# SENSORES.net
KiCad netlist of a schematic drawn in EAGLE
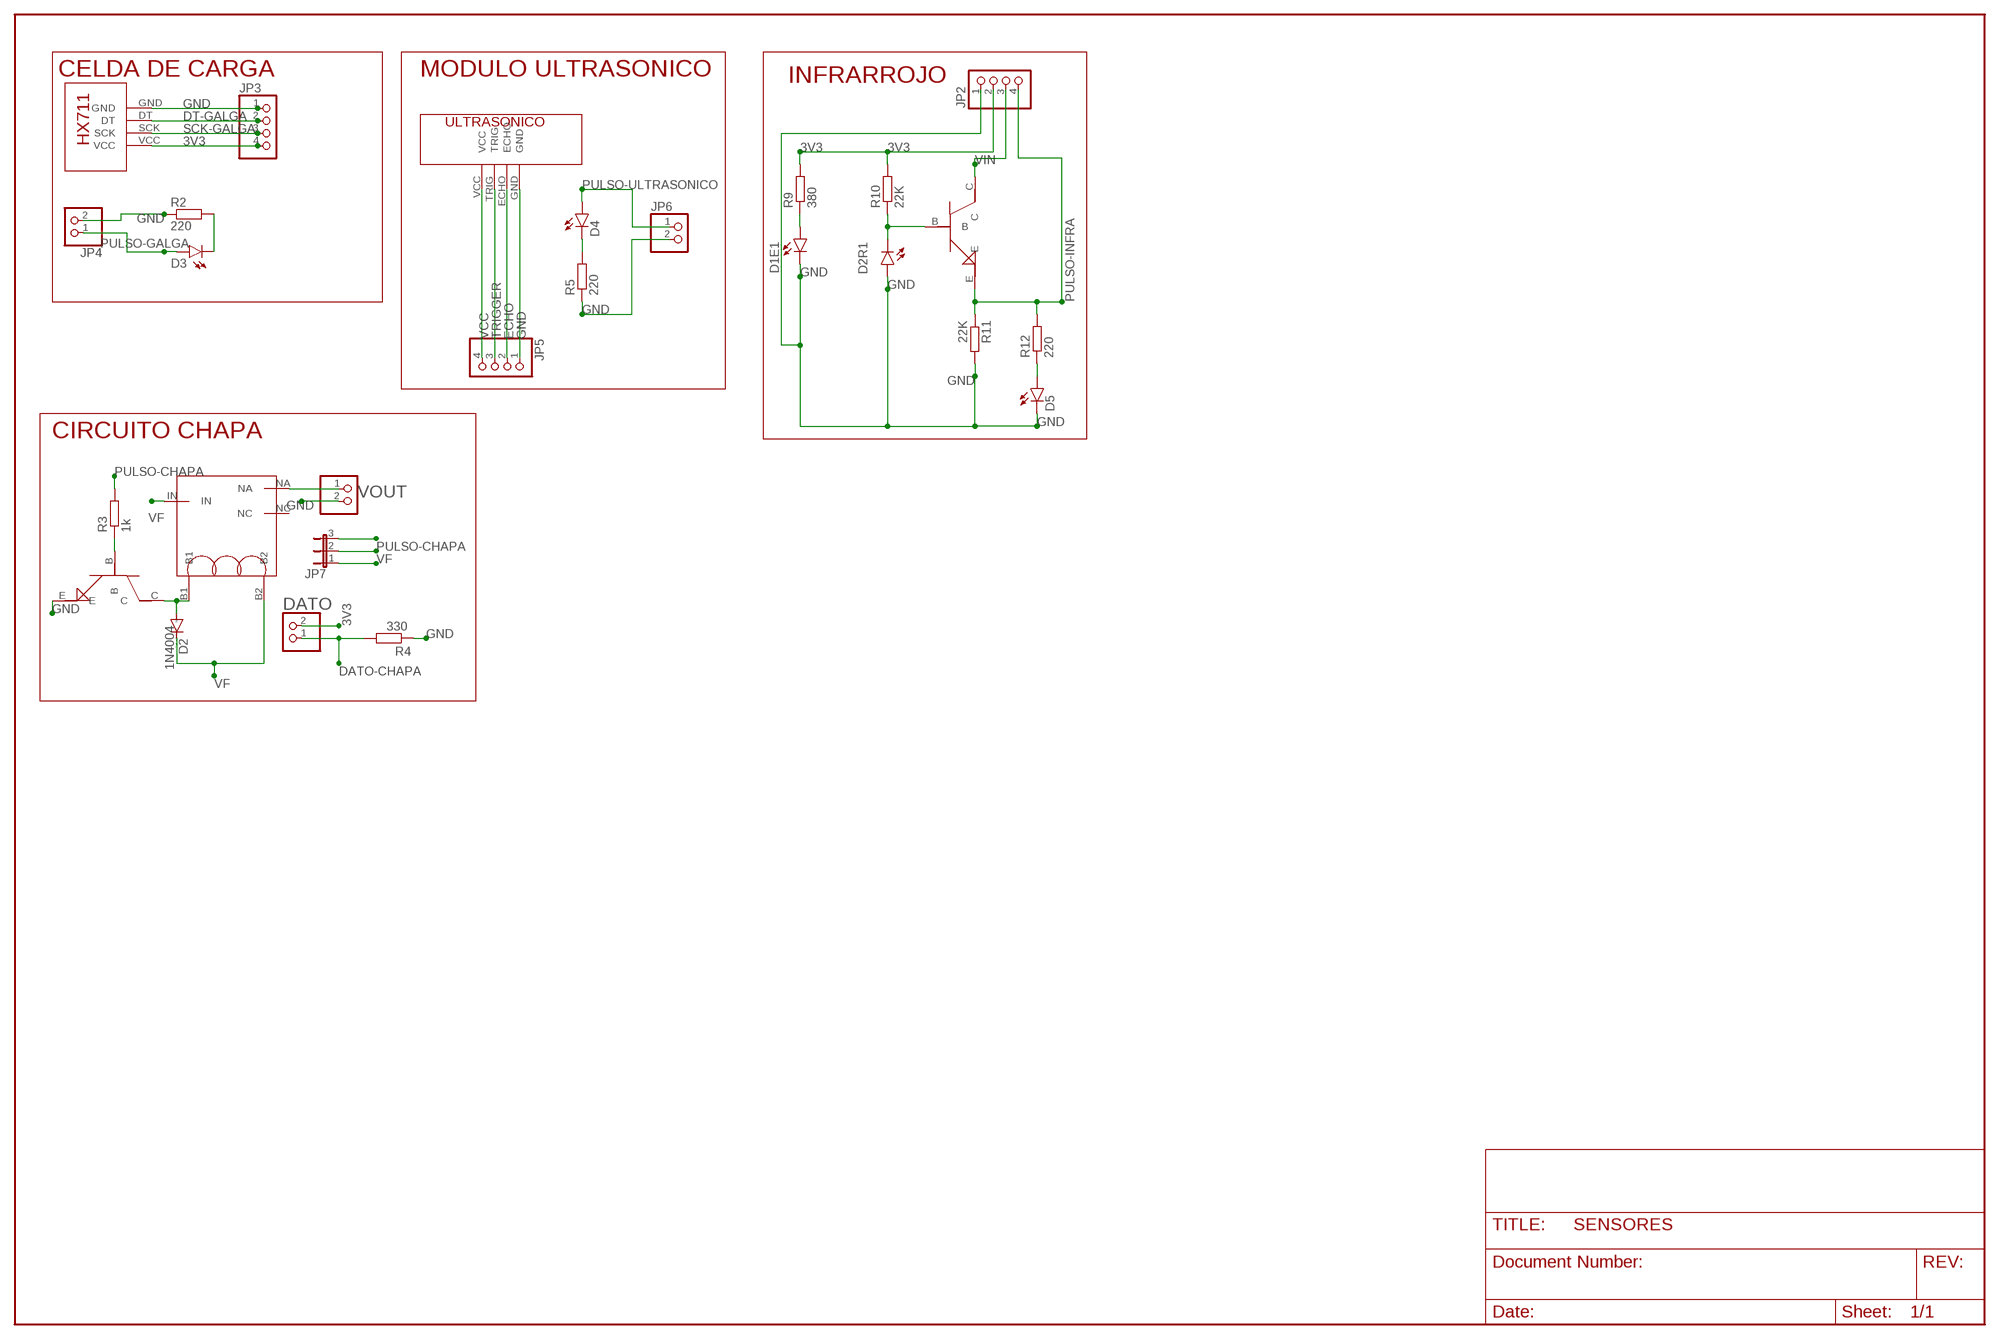
[diagram p0: schematic, sheet 1]

(export (version "E")
  (design (tool "Eeschema 10.0.6"))
  (components
    (comp (ref "D1E1")
      (value "LED3MM")
      (footprint "eagle-import:LED3MM")
      (libsource (lib "eagle-import") (part "LED3MM"))
    )
    (comp (ref "D2")
      (value "1N4004")
      (footprint "eagle-import:DO41-10")
      (libsource (lib "eagle-import") (part "1N4004"))
    )
    (comp (ref "D2R1")
      (value "LED3MM")
      (footprint "eagle-import:LED3MM")
      (libsource (lib "eagle-import") (part "LED3MM"))
    )
    (comp (ref "D3")
      (value "LED3MM")
      (footprint "eagle-import:LED3MM")
      (libsource (lib "eagle-import") (part "LED3MM"))
    )
    (comp (ref "D4")
      (value "LED3MM")
      (footprint "eagle-import:LED3MM")
      (libsource (lib "eagle-import") (part "LED3MM"))
    )
    (comp (ref "D5")
      (value "LED3MM")
      (footprint "eagle-import:LED3MM")
      (libsource (lib "eagle-import") (part "LED3MM"))
    )
    (comp (ref "DATO")
      (value "PINHD-1X2")
      (footprint "eagle-import:1X02")
      (libsource (lib "eagle-import") (part "PINHD-1X2"))
    )
    (comp (ref "JP2")
      (value "PINHD-1X4")
      (footprint "eagle-import:1X04")
      (libsource (lib "eagle-import") (part "PINHD-1X4"))
    )
    (comp (ref "JP3")
      (value "PINHD-1X4")
      (footprint "eagle-import:1X04")
      (libsource (lib "eagle-import") (part "PINHD-1X4"))
    )
    (comp (ref "JP4")
      (value "PINHD-1X2")
      (footprint "eagle-import:1X02")
      (libsource (lib "eagle-import") (part "PINHD-1X2"))
    )
    (comp (ref "JP5")
      (value "PINHD-1X4")
      (footprint "eagle-import:1X04")
      (libsource (lib "eagle-import") (part "PINHD-1X4"))
    )
    (comp (ref "JP6")
      (value "PINHD-1X2")
      (footprint "eagle-import:1X02")
      (libsource (lib "eagle-import") (part "PINHD-1X2"))
    )
    (comp (ref "JP7")
      (value "JP2E")
      (footprint "eagle-import:JP2")
      (libsource (lib "eagle-import") (part "JP2E"))
    )
    (comp (ref "R2")
      (value "220")
      (footprint "eagle-import:0204_7")
      (libsource (lib "eagle-import") (part "R-EU_0204/7"))
    )
    (comp (ref "R3")
      (value "1k")
      (footprint "eagle-import:0204_7")
      (libsource (lib "eagle-import") (part "R-EU_0204/7"))
    )
    (comp (ref "R4")
      (value "330")
      (footprint "eagle-import:0204_7")
      (libsource (lib "eagle-import") (part "R-EU_0204/7"))
    )
    (comp (ref "R5")
      (value "220")
      (footprint "eagle-import:0204_7")
      (libsource (lib "eagle-import") (part "R-EU_0204/7"))
    )
    (comp (ref "R9")
      (value "380")
      (footprint "eagle-import:0204_7")
      (libsource (lib "eagle-import") (part "R-EU_0204/7"))
    )
    (comp (ref "R10")
      (value "22K")
      (footprint "eagle-import:0204_7")
      (libsource (lib "eagle-import") (part "R-EU_0204/7"))
    )
    (comp (ref "R11")
      (value "22K")
      (footprint "eagle-import:0204_7")
      (libsource (lib "eagle-import") (part "R-EU_0204/7"))
    )
    (comp (ref "R12")
      (value "220")
      (footprint "eagle-import:0204_7")
      (libsource (lib "eagle-import") (part "R-EU_0204/7"))
    )
    (comp (ref "U$1")
      (value "HX-711")
      (footprint "eagle-import:HX-711")
      (libsource (lib "eagle-import") (part "HX-711"))
    )
    (comp (ref "U$2")
      (value "2N2222")
      (footprint "eagle-import:2N2222")
      (libsource (lib "eagle-import") (part "2N2222"))
    )
    (comp (ref "U$3")
      (value "ULTRASONICO")
      (footprint "eagle-import:ULTRASONICO")
      (libsource (lib "eagle-import") (part "ULTRASONICO"))
    )
    (comp (ref "U$5")
      (value "2N2222")
      (footprint "eagle-import:2N2222")
      (libsource (lib "eagle-import") (part "2N2222"))
    )
    (comp (ref "U$7")
      (value "RELEY")
      (footprint "eagle-import:RELEY")
      (libsource (lib "eagle-import") (part "RELEY"))
    )
    (comp (ref "VOUT")
      (value "PINHD-1X2")
      (footprint "eagle-import:1X02")
      (libsource (lib "eagle-import") (part "PINHD-1X2"))
    )
  )
  (nets
    (net (code "1") (name "/3V3") (class "Default")
      (node (ref "DATO") (pin "2") (pinfunction "2_2") (pintype "passive"))
      (node (ref "JP2") (pin "2") (pinfunction "2_2") (pintype "passive"))
      (node (ref "JP3") (pin "4") (pinfunction "4_4") (pintype "passive"))
      (node (ref "R10") (pin "2") (pinfunction "2_2") (pintype "passive"))
      (node (ref "R9") (pin "2") (pinfunction "2_2") (pintype "passive"))
      (node (ref "U$1") (pin "VCC") (pinfunction "VCC_VCC") (pintype "bidirectional"))
    )
    (net (code "2") (name "/DATO-CHAPA") (class "Default")
      (node (ref "DATO") (pin "1") (pinfunction "1_1") (pintype "passive"))
      (node (ref "R4") (pin "2") (pinfunction "2_2") (pintype "passive"))
    )
    (net (code "3") (name "/DT-GALGA") (class "Default")
      (node (ref "JP3") (pin "2") (pinfunction "2_2") (pintype "passive"))
      (node (ref "U$1") (pin "DT") (pinfunction "DT_DT") (pintype "bidirectional"))
    )
    (net (code "4") (name "/ECHO") (class "Default")
      (node (ref "JP5") (pin "2") (pinfunction "2_2") (pintype "passive"))
      (node (ref "U$3") (pin "ECHO") (pinfunction "ECHO_ECHO") (pintype "bidirectional"))
    )
    (net (code "5") (name "/GND") (class "Default")
      (node (ref "D1E1") (pin "K") (pinfunction "C_K") (pintype "passive"))
      (node (ref "D2R1") (pin "A") (pinfunction "A_A") (pintype "passive"))
      (node (ref "D5") (pin "K") (pinfunction "C_K") (pintype "passive"))
      (node (ref "JP2") (pin "1") (pinfunction "1_1") (pintype "passive"))
      (node (ref "JP3") (pin "1") (pinfunction "1_1") (pintype "passive"))
      (node (ref "JP4") (pin "2") (pinfunction "2_2") (pintype "passive"))
      (node (ref "JP5") (pin "1") (pinfunction "1_1") (pintype "passive"))
      (node (ref "JP6") (pin "2") (pinfunction "2_2") (pintype "passive"))
      (node (ref "JP7") (pin "3") (pinfunction "3_3") (pintype "passive"))
      (node (ref "R11") (pin "2") (pinfunction "2_2") (pintype "passive"))
      (node (ref "R2") (pin "1") (pinfunction "1_1") (pintype "passive"))
      (node (ref "R4") (pin "1") (pinfunction "1_1") (pintype "passive"))
      (node (ref "R5") (pin "1") (pinfunction "1_1") (pintype "passive"))
      (node (ref "U$1") (pin "GND") (pinfunction "GND_GND") (pintype "bidirectional"))
      (node (ref "U$3") (pin "GND") (pinfunction "GND_GND") (pintype "bidirectional"))
      (node (ref "U$5") (pin "E") (pinfunction "E_E") (pintype "bidirectional"))
      (node (ref "VOUT") (pin "2") (pinfunction "2_2") (pintype "passive"))
    )
    (net (code "6") (name "/PULSO-CHAPA") (class "Default")
      (node (ref "JP7") (pin "2") (pinfunction "2_2") (pintype "passive"))
      (node (ref "R3") (pin "2") (pinfunction "2_2") (pintype "passive"))
    )
    (net (code "7") (name "/PULSO-GALGA") (class "Default")
      (node (ref "D3") (pin "A") (pinfunction "A_A") (pintype "passive"))
      (node (ref "JP4") (pin "1") (pinfunction "1_1") (pintype "passive"))
    )
    (net (code "8") (name "/PULSO-INFRA") (class "Default")
      (node (ref "JP2") (pin "4") (pinfunction "4_4") (pintype "passive"))
      (node (ref "R11") (pin "1") (pinfunction "1_1") (pintype "passive"))
      (node (ref "R12") (pin "2") (pinfunction "2_2") (pintype "passive"))
      (node (ref "U$2") (pin "E") (pinfunction "E_E") (pintype "bidirectional"))
    )
    (net (code "9") (name "/PULSO-ULTRASONICO") (class "Default")
      (node (ref "D4") (pin "A") (pinfunction "A_A") (pintype "passive"))
      (node (ref "JP6") (pin "1") (pinfunction "1_1") (pintype "passive"))
    )
    (net (code "10") (name "/SCK-GALGA") (class "Default")
      (node (ref "JP3") (pin "3") (pinfunction "3_3") (pintype "passive"))
      (node (ref "U$1") (pin "SCK") (pinfunction "SCK_SCK") (pintype "bidirectional"))
    )
    (net (code "11") (name "/TRIGGER") (class "Default")
      (node (ref "JP5") (pin "3") (pinfunction "3_3") (pintype "passive"))
      (node (ref "U$3") (pin "TRIG") (pinfunction "TRIG_TRIG") (pintype "bidirectional"))
    )
    (net (code "12") (name "/VCC") (class "Default")
      (node (ref "JP5") (pin "4") (pinfunction "4_4") (pintype "passive"))
      (node (ref "U$3") (pin "VCC") (pinfunction "VCC_VCC") (pintype "bidirectional"))
    )
    (net (code "13") (name "/VF") (class "Default")
      (node (ref "D2") (pin "C") (pinfunction "C_C") (pintype "passive"))
      (node (ref "JP7") (pin "1") (pinfunction "1_1") (pintype "passive"))
      (node (ref "U$7") (pin "B2") (pinfunction "B2_B2") (pintype "bidirectional"))
      (node (ref "U$7") (pin "IN") (pinfunction "IN_IN") (pintype "bidirectional"))
    )
    (net (code "14") (name "/VIN") (class "Default")
      (node (ref "JP2") (pin "3") (pinfunction "3_3") (pintype "passive"))
      (node (ref "U$2") (pin "C") (pinfunction "C_C") (pintype "bidirectional"))
    )
    (net (code "15") (name "Net-(D1E1-PadA)") (class "Default")
      (node (ref "D1E1") (pin "A") (pinfunction "A_A") (pintype "passive"))
      (node (ref "R9") (pin "1") (pinfunction "1_1") (pintype "passive"))
    )
    (net (code "16") (name "Net-(D2-PadA)") (class "Default")
      (node (ref "D2") (pin "A") (pinfunction "A_A") (pintype "passive"))
      (node (ref "U$5") (pin "C") (pinfunction "C_C") (pintype "bidirectional"))
      (node (ref "U$7") (pin "B1") (pinfunction "B1_B1") (pintype "bidirectional"))
    )
    (net (code "17") (name "Net-(D2R1-C)") (class "Default")
      (node (ref "D2R1") (pin "K") (pinfunction "C_K") (pintype "passive"))
      (node (ref "R10") (pin "1") (pinfunction "1_1") (pintype "passive"))
      (node (ref "U$2") (pin "B") (pinfunction "B_B") (pintype "bidirectional"))
    )
    (net (code "18") (name "Net-(D3-C)") (class "Default")
      (node (ref "D3") (pin "K") (pinfunction "C_K") (pintype "passive"))
      (node (ref "R2") (pin "2") (pinfunction "2_2") (pintype "passive"))
    )
    (net (code "19") (name "Net-(D4-C)") (class "Default")
      (node (ref "D4") (pin "K") (pinfunction "C_K") (pintype "passive"))
      (node (ref "R5") (pin "2") (pinfunction "2_2") (pintype "passive"))
    )
    (net (code "20") (name "Net-(D5-PadA)") (class "Default")
      (node (ref "D5") (pin "A") (pinfunction "A_A") (pintype "passive"))
      (node (ref "R12") (pin "1") (pinfunction "1_1") (pintype "passive"))
    )
    (net (code "21") (name "Net-(R3-Pad1)") (class "Default")
      (node (ref "R3") (pin "1") (pinfunction "1_1") (pintype "passive"))
      (node (ref "U$5") (pin "B") (pinfunction "B_B") (pintype "bidirectional"))
    )
    (net (code "22") (name "Net-(U$7-PadNA)") (class "Default")
      (node (ref "U$7") (pin "NA") (pinfunction "NA_NA") (pintype "bidirectional"))
      (node (ref "VOUT") (pin "1") (pinfunction "1_1") (pintype "passive"))
    )
    (net (code "23") (name "unconnected-(U$7-PadNC)") (class "Default")
      (node (ref "U$7") (pin "NC") (pinfunction "NC_NC") (pintype "bidirectional"))
    )
  )
)
